# amp-LNA-TQP3M903x.net
KiCad netlist of a schematic drawn in EAGLE
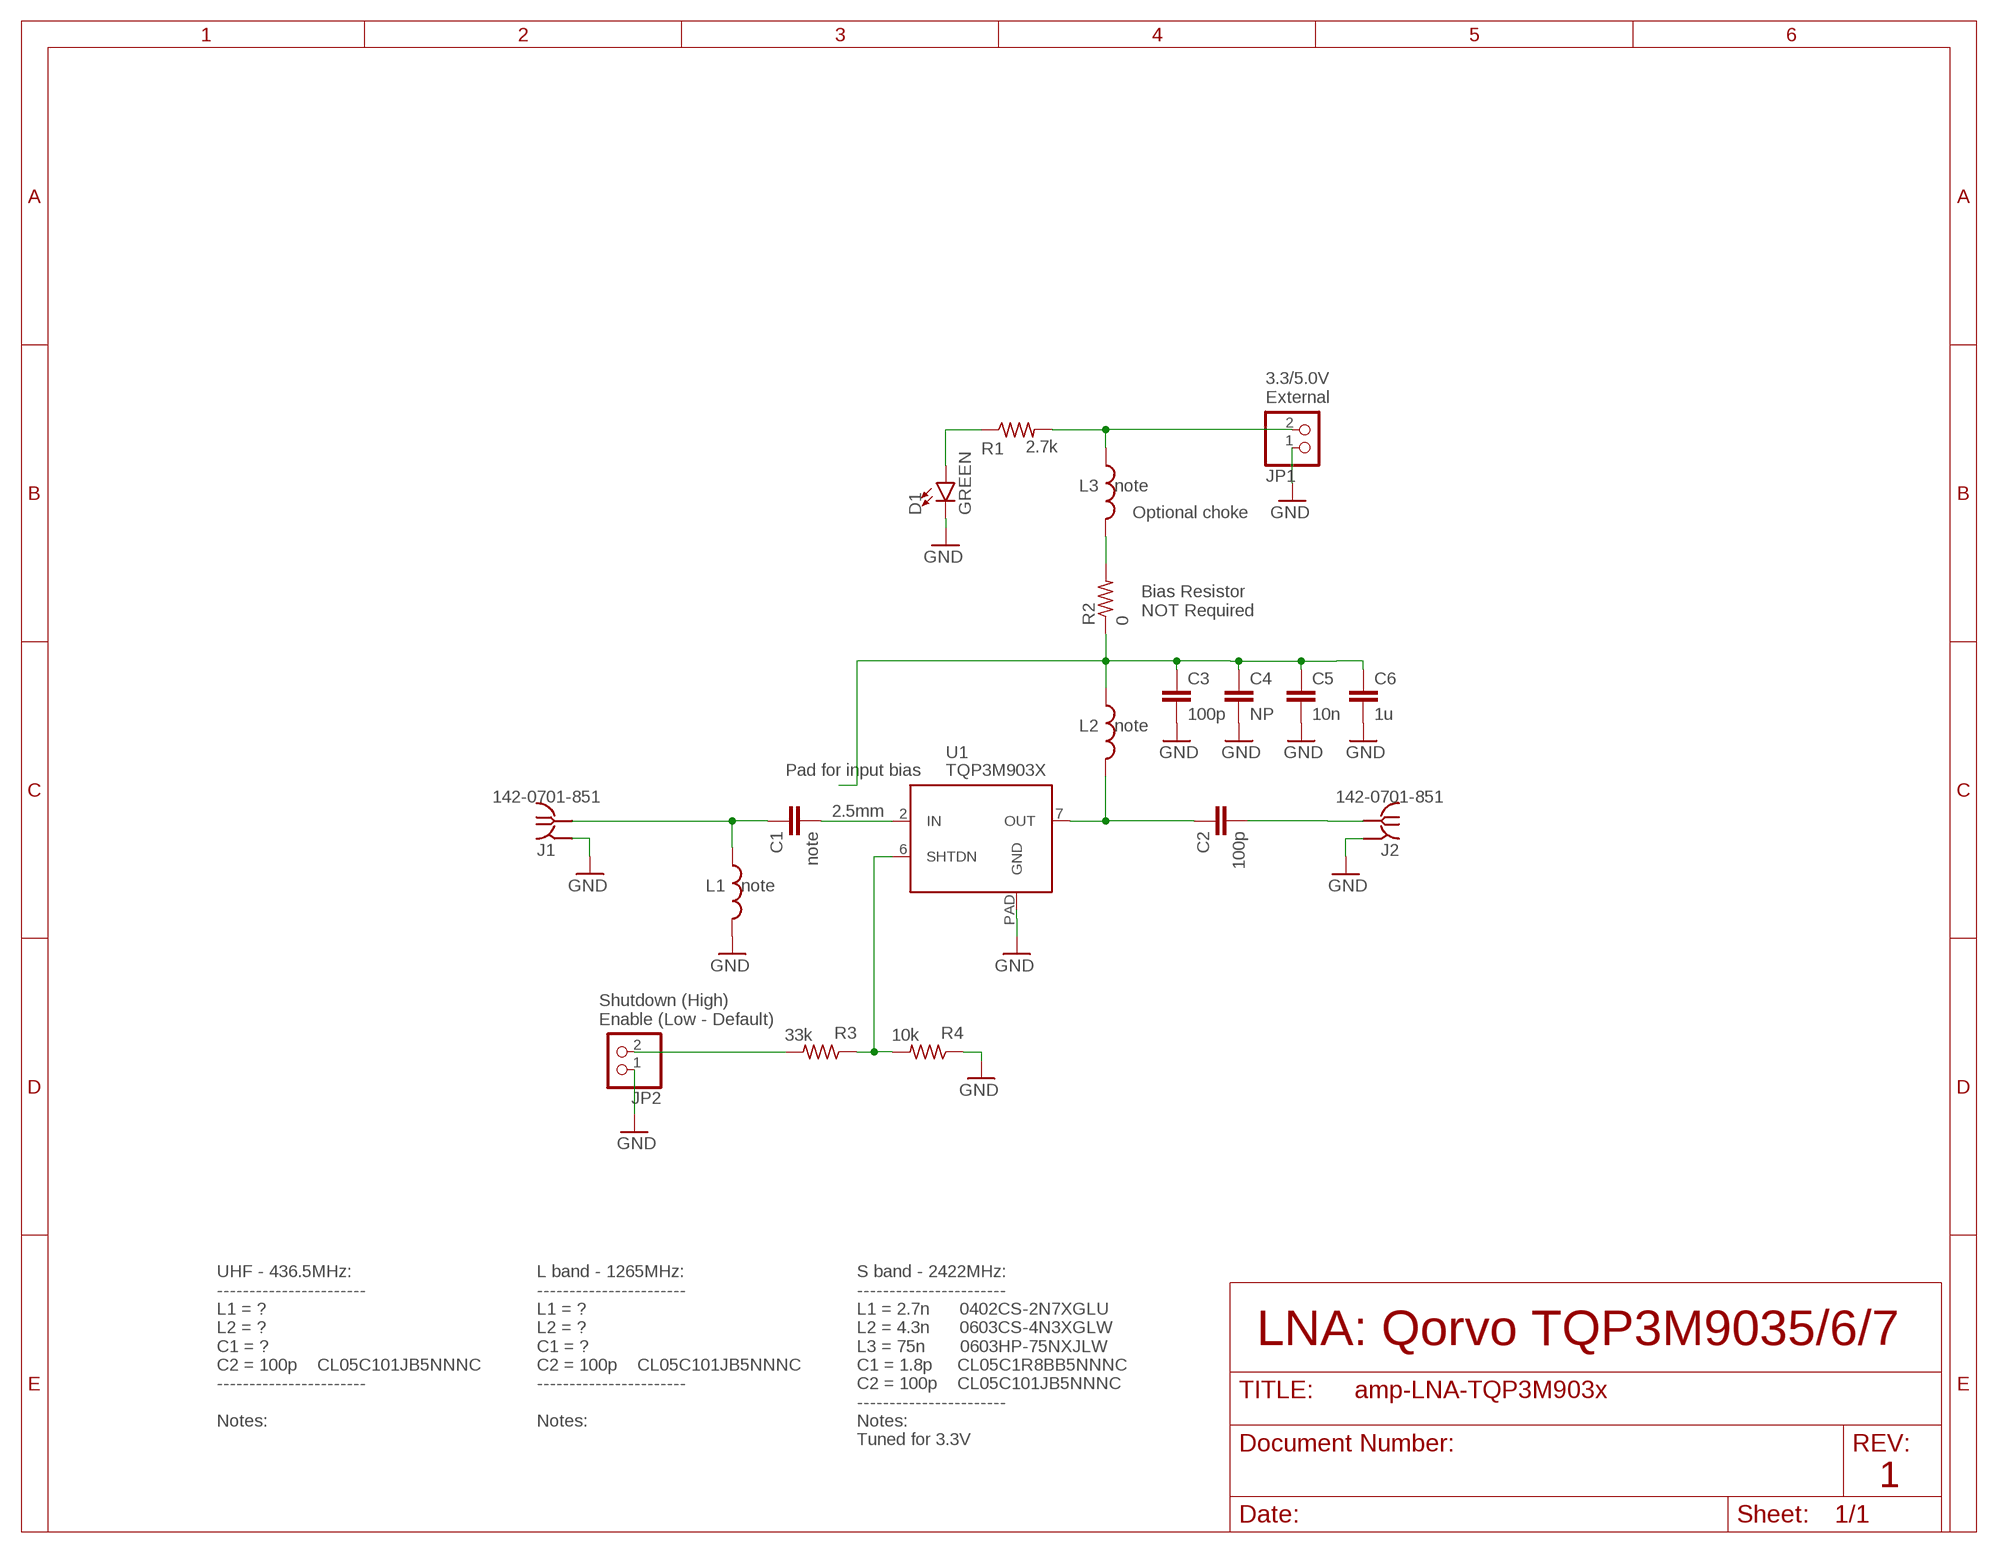
[diagram p0: schematic, sheet 1]

(export (version "E")
  (design (tool "Eeschema 10.0.6"))
  (components
    (comp (ref "C1")
      (value "note")
      (footprint "eagle-import:.0402-C-NOSILK")
      (libsource (lib "eagle-import") (part "C-EU0402-C-NOSILK"))
    )
    (comp (ref "C2")
      (value "100p")
      (footprint "eagle-import:.0402-C-NOSILK")
      (libsource (lib "eagle-import") (part "C-EU0402-C-NOSILK"))
    )
    (comp (ref "C3")
      (value "100p")
      (footprint "eagle-import:.0603-B-NOSILK")
      (libsource (lib "eagle-import") (part "C-EU0603-B-NOSILK"))
    )
    (comp (ref "C4")
      (value "NP")
      (footprint "eagle-import:.0603-B-NOSILK")
      (libsource (lib "eagle-import") (part "C-EU0603-B-NOSILK"))
    )
    (comp (ref "C5")
      (value "10n")
      (footprint "eagle-import:.0603-B-NOSILK")
      (libsource (lib "eagle-import") (part "C-EU0603-B-NOSILK"))
    )
    (comp (ref "C6")
      (value "1u")
      (footprint "eagle-import:.0603-B-NOSILK")
      (libsource (lib "eagle-import") (part "C-EU0603-B-NOSILK"))
    )
    (comp (ref "D1")
      (value "GREEN")
      (footprint "eagle-import:LED-0603")
      (libsource (lib "eagle-import") (part "LED-GREEN0603"))
    )
    (comp (ref "J1")
      (value "142-0701-851")
      (footprint "eagle-import:142-0701-851")
      (libsource (lib "eagle-import") (part "142-0701-851"))
    )
    (comp (ref "J2")
      (value "142-0701-851")
      (footprint "eagle-import:142-0701-851")
      (libsource (lib "eagle-import") (part "142-0701-851"))
    )
    (comp (ref "JP1")
      (value "PINHD-1X2")
      (footprint "eagle-import:1X02")
      (libsource (lib "eagle-import") (part "PINHD-1X2"))
    )
    (comp (ref "JP2")
      (value "PINHD-1X2")
      (footprint "eagle-import:1X02")
      (libsource (lib "eagle-import") (part "PINHD-1X2"))
    )
    (comp (ref "L1")
      (value "note")
      (footprint "eagle-import:.0402-C-NOSILK")
      (libsource (lib "eagle-import") (part "L-US0402-C-NOSILK"))
    )
    (comp (ref "L2")
      (value "note")
      (footprint "eagle-import:.0603-C-NOSILK")
      (libsource (lib "eagle-import") (part "L-US0603-C-NOSILK"))
    )
    (comp (ref "L3")
      (value "note")
      (footprint "eagle-import:.0603-B-NOSILK")
      (libsource (lib "eagle-import") (part "L-US0603-B-NOSILK"))
    )
    (comp (ref "R1")
      (value "2.7k")
      (footprint "eagle-import:.0603-B-NOSILK")
      (libsource (lib "eagle-import") (part "R-US_0603-B-NOSILK"))
    )
    (comp (ref "R2")
      (value "0")
      (footprint "eagle-import:.0603-B-NOSILK")
      (libsource (lib "eagle-import") (part "R-US_0603-B-NOSILK"))
    )
    (comp (ref "R3")
      (value "33k")
      (footprint "eagle-import:.0603-B-NOSILK")
      (libsource (lib "eagle-import") (part "R-US_0603-B-NOSILK"))
    )
    (comp (ref "R4")
      (value "10k")
      (footprint "eagle-import:.0603-B-NOSILK")
      (libsource (lib "eagle-import") (part "R-US_0603-B-NOSILK"))
    )
    (comp (ref "U1")
      (value "TQP3M903X")
      (footprint "eagle-import:DFN8-2X2-WITH-PAD")
      (libsource (lib "eagle-import") (part "TQP3M903X"))
    )
  )
  (nets
    (net (code "1") (name "GND") (class "Default")
      (node (ref "C3") (pin "2") (pinfunction "2_2") (pintype "passive"))
      (node (ref "C4") (pin "2") (pinfunction "2_2") (pintype "passive"))
      (node (ref "C5") (pin "2") (pinfunction "2_2") (pintype "passive"))
      (node (ref "C6") (pin "2") (pinfunction "2_2") (pintype "passive"))
      (node (ref "D1") (pin "C") (pinfunction "C_C") (pintype "passive"))
      (node (ref "J1") (pin "GND1") (pinfunction "GND_GND1") (pintype "bidirectional"))
      (node (ref "J1") (pin "GND2") (pinfunction "GND_GND2") (pintype "bidirectional"))
      (node (ref "J1") (pin "GND3") (pinfunction "GND_GND3") (pintype "bidirectional"))
      (node (ref "J1") (pin "GND4") (pinfunction "GND_GND4") (pintype "bidirectional"))
      (node (ref "J2") (pin "GND1") (pinfunction "GND_GND1") (pintype "bidirectional"))
      (node (ref "J2") (pin "GND2") (pinfunction "GND_GND2") (pintype "bidirectional"))
      (node (ref "J2") (pin "GND3") (pinfunction "GND_GND3") (pintype "bidirectional"))
      (node (ref "J2") (pin "GND4") (pinfunction "GND_GND4") (pintype "bidirectional"))
      (node (ref "JP1") (pin "1") (pinfunction "1_1") (pintype "passive"))
      (node (ref "JP2") (pin "1") (pinfunction "1_1") (pintype "passive"))
      (node (ref "L1") (pin "2") (pinfunction "2_2") (pintype "passive"))
      (node (ref "R4") (pin "1") (pinfunction "1_1") (pintype "passive"))
      (node (ref "U1") (pin "PAD") (pinfunction "GND_PAD") (pintype "power_in"))
    )
    (net (code "2") (name "Net-(C3-Pad1)") (class "Default")
      (node (ref "C3") (pin "1") (pinfunction "1_1") (pintype "passive"))
      (node (ref "C4") (pin "1") (pinfunction "1_1") (pintype "passive"))
      (node (ref "C5") (pin "1") (pinfunction "1_1") (pintype "passive"))
      (node (ref "C6") (pin "1") (pinfunction "1_1") (pintype "passive"))
      (node (ref "L2") (pin "1") (pinfunction "1_1") (pintype "passive"))
      (node (ref "R2") (pin "1") (pinfunction "1_1") (pintype "passive"))
    )
    (net (code "3") (name "Net-(D1-PadA)") (class "Default")
      (node (ref "D1") (pin "A") (pinfunction "A_A") (pintype "passive"))
      (node (ref "R1") (pin "1") (pinfunction "1_1") (pintype "passive"))
    )
    (net (code "4") (name "Net-(J1-RF)") (class "Default")
      (node (ref "C1") (pin "1") (pinfunction "1_1") (pintype "passive"))
      (node (ref "J1") (pin "RF1") (pinfunction "RF_RF1") (pintype "bidirectional"))
      (node (ref "L1") (pin "1") (pinfunction "1_1") (pintype "passive"))
    )
    (net (code "5") (name "Net-(J2-RF)") (class "Default")
      (node (ref "C2") (pin "2") (pinfunction "2_2") (pintype "passive"))
      (node (ref "J2") (pin "RF1") (pinfunction "RF_RF1") (pintype "bidirectional"))
    )
    (net (code "6") (name "Net-(JP1-Pad2)") (class "Default")
      (node (ref "JP1") (pin "2") (pinfunction "2_2") (pintype "passive"))
      (node (ref "L3") (pin "1") (pinfunction "1_1") (pintype "passive"))
      (node (ref "R1") (pin "2") (pinfunction "2_2") (pintype "passive"))
    )
    (net (code "7") (name "Net-(JP2-Pad2)") (class "Default")
      (node (ref "JP2") (pin "2") (pinfunction "2_2") (pintype "passive"))
      (node (ref "R3") (pin "2") (pinfunction "2_2") (pintype "passive"))
    )
    (net (code "8") (name "Net-(L3-Pad2)") (class "Default")
      (node (ref "L3") (pin "2") (pinfunction "2_2") (pintype "passive"))
      (node (ref "R2") (pin "2") (pinfunction "2_2") (pintype "passive"))
    )
    (net (code "9") (name "Net-(U1-IN)") (class "Default")
      (node (ref "C1") (pin "2") (pinfunction "2_2") (pintype "passive"))
      (node (ref "U1") (pin "2") (pinfunction "IN_2") (pintype "input"))
    )
    (net (code "10") (name "Net-(U1-OUT)") (class "Default")
      (node (ref "C2") (pin "1") (pinfunction "1_1") (pintype "passive"))
      (node (ref "L2") (pin "2") (pinfunction "2_2") (pintype "passive"))
      (node (ref "U1") (pin "7") (pinfunction "OUT_7") (pintype "output"))
    )
    (net (code "11") (name "Net-(U1-SHTDN)") (class "Default")
      (node (ref "R3") (pin "1") (pinfunction "1_1") (pintype "passive"))
      (node (ref "R4") (pin "2") (pinfunction "2_2") (pintype "passive"))
      (node (ref "U1") (pin "6") (pinfunction "SHTDN_6") (pintype "input"))
    )
  )
)
